# scheme-mkii.net
KiCad netlist of a schematic drawn in Altium Designer
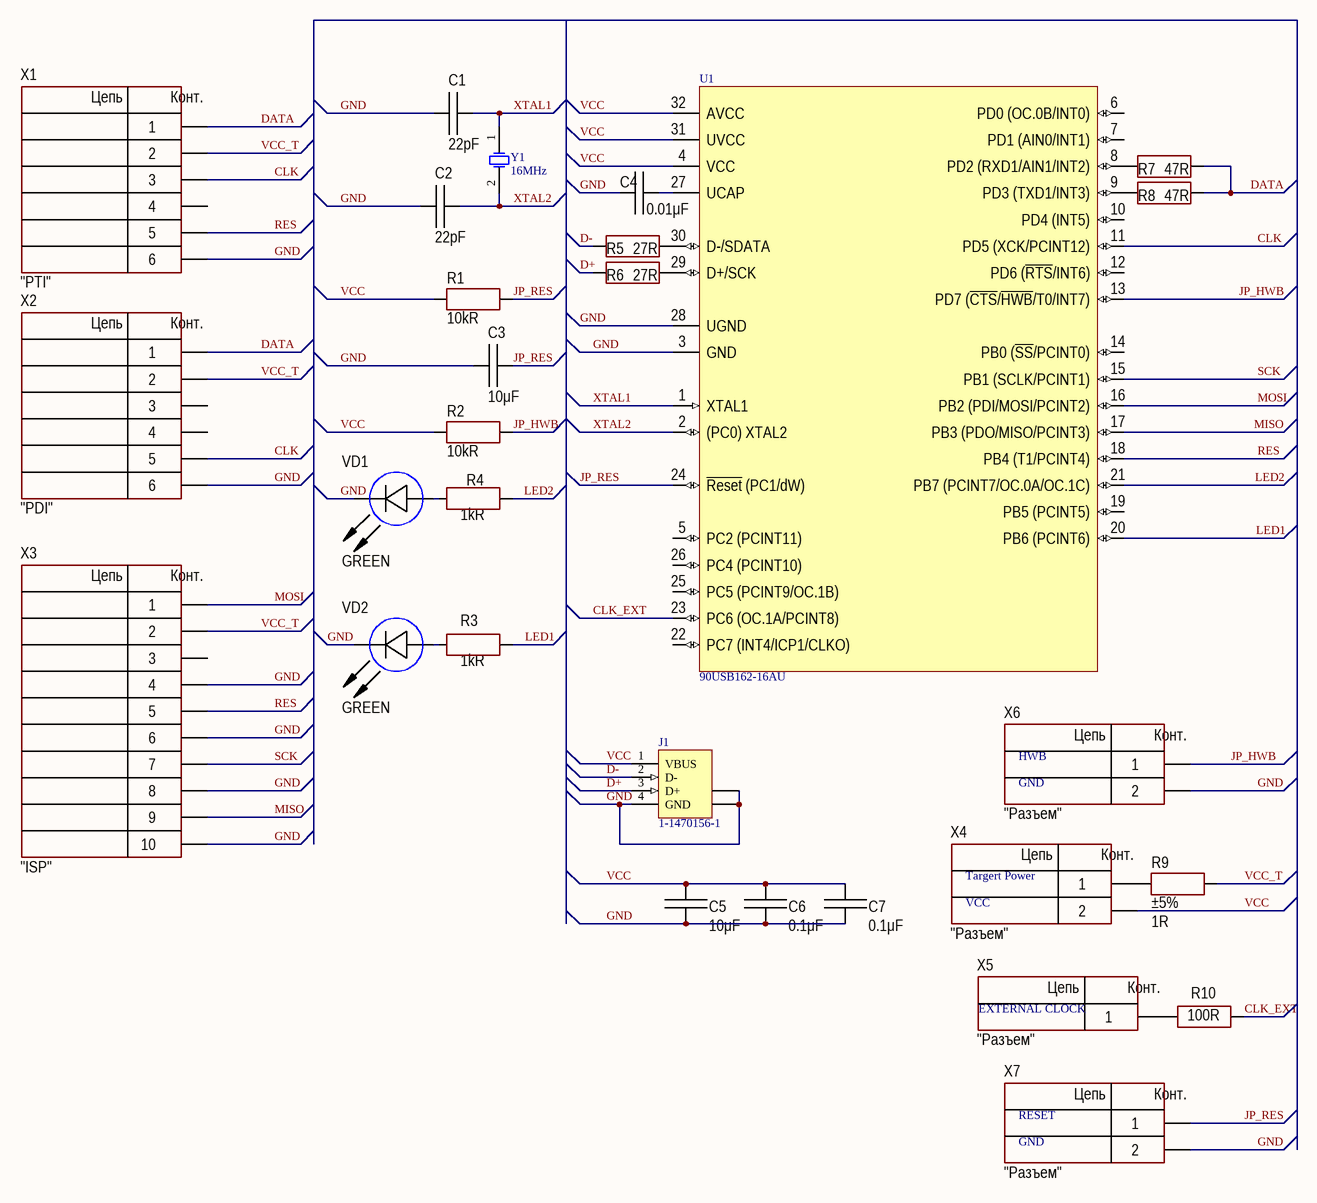
[diagram p0: scheme-mkii.SchDoc]

(export (version "E")
  (design (tool "Eeschema 10.0.6"))
  (components
    (comp (ref "C1")
      (value "22pF")
      (footprint "CAP: 0805")
      (fields
        (field (name "MANUFACTURER") "Yageo")
        (field (name "PARTNUMBER") "CC0805KRX7R7BB104")
        (field (name "VALUEMANUFACTURERPARTNUMBER") "Ceramic capacitor, 22pF, X7R, ±10%, 16V, 0805, -55...+125°C")
      )
      (libsource (lib "Capacitor") (part "Ceramic_0805"))
    )
    (comp (ref "C2")
      (value "22pF")
      (footprint "CAP: 0805")
      (fields
        (field (name "MANUFACTURER") "Yageo")
        (field (name "PARTNUMBER") "CC0805KRX7R7BB104")
        (field (name "VALUEMANUFACTURERPARTNUMBER") "Ceramic capacitor, 22pF, X7R, ±10%, 16V, 0805, -55...+125°C")
      )
      (libsource (lib "Capacitor") (part "Ceramic_0805"))
    )
    (comp (ref "C3")
      (value "10μF")
      (footprint "CAP: 0805")
      (fields
        (field (name "MANUFACTURER") "Yageo")
        (field (name "PARTNUMBER") "CC0805KRX7R7BB104")
        (field (name "VALUEMANUFACTURERPARTNUMBER") "Ceramic capacitor, 10μF, X7R, ±10%, 16V, 0805, -55...+125°C")
      )
      (libsource (lib "Capacitor") (part "Ceramic_0805"))
    )
    (comp (ref "C4")
      (value "0.01μF")
      (footprint "CAP: 0805")
      (fields
        (field (name "MANUFACTURER") "Yageo")
        (field (name "PARTNUMBER") "CC0805KRX7R7BB104")
        (field (name "VALUEMANUFACTURERPARTNUMBER") "Ceramic capacitor, 0.01μF, X7R, ±10%, 16V, 0805, -55...+125°C")
      )
      (libsource (lib "Capacitor") (part "Ceramic_0805"))
    )
    (comp (ref "C5")
      (value "10μF")
      (footprint "CAP: 0805")
      (fields
        (field (name "MANUFACTURER") "Yageo")
        (field (name "PARTNUMBER") "CC0805KRX7R7BB104")
        (field (name "VALUEMANUFACTURERPARTNUMBER") "Ceramic capacitor, 10μF, X7R, ±10%, 16V, 0805, -55...+125°C")
      )
      (libsource (lib "Capacitor") (part "Ceramic_0805"))
    )
    (comp (ref "C6")
      (value "0.1μF")
      (footprint "CAP: 0805")
      (fields
        (field (name "MANUFACTURER") "Yageo")
        (field (name "PARTNUMBER") "CC0805KRX7R7BB104")
        (field (name "VALUEMANUFACTURERPARTNUMBER") "Ceramic capacitor, 0.1μF, X7R, ±10%, 16V, 0805, -55...+125°C")
      )
      (libsource (lib "Capacitor") (part "Ceramic_0805"))
    )
    (comp (ref "C7")
      (value "0.1μF")
      (footprint "CAP: 0805")
      (fields
        (field (name "MANUFACTURER") "Yageo")
        (field (name "PARTNUMBER") "CC0805KRX7R7BB104")
        (field (name "VALUEMANUFACTURERPARTNUMBER") "Ceramic capacitor, 0.1μF, X7R, ±10%, 16V, 0805, -55...+125°C")
      )
      (libsource (lib "Capacitor") (part "Ceramic_0805"))
    )
    (comp (ref "J1")
      (value "1-1470156-1")
      (footprint "1-1470156")
      (description "USB 1.1, Right Angle, Thru-Hole, B Type, Receptacle, 4 Position, White")
      (fields (field (name "PUBLISHER") "Altium Limited"))
      (libsource (lib "AMP Serial Bus USB") (part "1-1470156-1"))
    )
    (comp (ref "R1")
      (value "10kR")
      (footprint "RES: 0402")
      (fields
        (field (name "MANUFACTURER") "Yageo")
        (field (name "PARTNUMBER") "RC0402JR-07100RL")
        (field (name "VALUEMANUFACTURERPARTNUMBER") "Resistor film, 10kR, ±5%, 0402, 0.063W, -55...+125°C")
      )
      (libsource (lib "") (part "Resistor_0402_1"))
    )
    (comp (ref "R2")
      (value "10kR")
      (footprint "RES: 0402")
      (fields
        (field (name "MANUFACTURER") "Yageo")
        (field (name "PARTNUMBER") "RC0402JR-07100RL")
        (field (name "VALUEMANUFACTURERPARTNUMBER") "Resistor film, 10kR, ±5%, 0402, 0.063W, -55...+125°C")
      )
      (libsource (lib "") (part "Resistor_0402_1"))
    )
    (comp (ref "R3")
      (value "1kR")
      (footprint "RES: 0402")
      (fields
        (field (name "MANUFACTURER") "Yageo")
        (field (name "PARTNUMBER") "RC0402JR-07100RL")
        (field (name "VALUEMANUFACTURERPARTNUMBER") "Resistor film, 1kR, ±5%, 0402, 0.063W, -55...+125°C")
      )
      (libsource (lib "Resistor") (part "Resistor_0402"))
    )
    (comp (ref "R4")
      (value "1kR")
      (footprint "RES: 0402")
      (fields
        (field (name "MANUFACTURER") "Yageo")
        (field (name "PARTNUMBER") "RC0402JR-07100RL")
        (field (name "VALUEMANUFACTURERPARTNUMBER") "Resistor film, 1kR, ±5%, 0402, 0.063W, -55...+125°C")
      )
      (libsource (lib "Resistor") (part "Resistor_0402"))
    )
    (comp (ref "R5")
      (value "27R")
      (footprint "RES: 0402")
      (fields
        (field (name "MANUFACTURER") "Yageo")
        (field (name "PARTNUMBER") "RC0402JR-07100RL")
        (field (name "VALUEMANUFACTURERPARTNUMBER") "Resistor film, 27R, ±5%, 0402, 0.063W, -55...+125°C")
      )
      (libsource (lib "Resistor") (part "Resistor_0402"))
    )
    (comp (ref "R6")
      (value "27R")
      (footprint "RES: 0402")
      (fields
        (field (name "MANUFACTURER") "Yageo")
        (field (name "PARTNUMBER") "RC0402JR-07100RL")
        (field (name "VALUEMANUFACTURERPARTNUMBER") "Resistor film, 27R, ±5%, 0402, 0.063W, -55...+125°C")
      )
      (libsource (lib "Resistor") (part "Resistor_0402"))
    )
    (comp (ref "R7")
      (value "47R")
      (footprint "RES: 0402")
      (fields
        (field (name "MANUFACTURER") "Yageo")
        (field (name "PARTNUMBER") "RC0402JR-07100RL")
        (field (name "VALUEMANUFACTURERPARTNUMBER") "Resistor film, 47R, ±5%, 0402, 0.063W, -55...+125°C")
      )
      (libsource (lib "Resistor") (part "Resistor_0402"))
    )
    (comp (ref "R8")
      (value "47R")
      (footprint "RES: 0402")
      (fields
        (field (name "MANUFACTURER") "Yageo")
        (field (name "PARTNUMBER") "RC0402JR-07100RL")
        (field (name "VALUEMANUFACTURERPARTNUMBER") "Resistor film, 47R, ±5%, 0402, 0.063W, -55...+125°C")
      )
      (libsource (lib "Resistor") (part "Resistor_0402"))
    )
    (comp (ref "R9")
      (value "1R")
      (footprint "RES: 0402")
      (fields
        (field (name "MANUFACTURER") "Yageo")
        (field (name "PARTNUMBER") "RC0402JR-07100RL")
        (field (name "VALUEMANUFACTURERPARTNUMBER") "Resistor film, 1R, ±5%, 0402, 0.063W, -55...+125°C")
        (field (name "TOLERANCE") "±5%")
      )
      (libsource (lib "Resistor") (part "Resistor_0402"))
    )
    (comp (ref "R10")
      (value "100R")
      (footprint "RES: 0402")
      (fields
        (field (name "MANUFACTURER") "Yageo")
        (field (name "PARTNUMBER") "RC0402JR-07100RL")
        (field (name "VALUEMANUFACTURERPARTNUMBER") "Resistor film, 100R, ±5%, 0402, 0.063W, -55...+125°C")
      )
      (libsource (lib "Resistor") (part "Resistor_0402"))
    )
    (comp (ref "U1")
      (value "90USB162-16AU")
      (footprint "32MA_N")
      (libsource (lib "Atmel Microcontroller megaAVR") (part "90USB162-16AU"))
    )
    (comp (ref "VD1")
      (value "~")
      (footprint "LED: 0402B")
      (fields
        (field (name "VALUEMANUFACTURERPARTNUMBER") "LED, *, *, *, -55...+150°C")
        (field (name "COLOR") "GREEN")
      )
      (libsource (lib "Diode") (part "LED_single"))
    )
    (comp (ref "VD2")
      (value "~")
      (footprint "LED: 0402B")
      (fields
        (field (name "VALUEMANUFACTURERPARTNUMBER") "LED, *, *, *, -55...+150°C")
        (field (name "COLOR") "GREEN")
      )
      (libsource (lib "Diode") (part "LED_single"))
    )
    (comp (ref "X1")
      (value "~")
      (footprint "CON: IDC-6MS")
      (fields
        (field (name "MANUFACTURER") "Connfly")
        (field (name "VALUEMANUFACTURERPARTNUMBER") "Connector, 6pin, 2.54mm, 250VAC, 3A")
        (field (name "PARTNUMBER") "IDC-6")
        (field (name "COMMENTTEXT") "\"PTI\"")
      )
      (libsource (lib "Connector") (part "IDC-6"))
    )
    (comp (ref "X2")
      (value "~")
      (footprint "CON: IDC-6MS")
      (fields
        (field (name "MANUFACTURER") "Connfly")
        (field (name "VALUEMANUFACTURERPARTNUMBER") "Connector, 6pin, 2.54mm, 250VAC, 3A")
        (field (name "PARTNUMBER") "IDC-6")
        (field (name "COMMENTTEXT") "\"PDI\"")
      )
      (libsource (lib "Connector") (part "IDC-6"))
    )
    (comp (ref "X3")
      (value "~")
      (footprint "CON: IDC-10MS")
      (fields
        (field (name "MANUFACTURER") "Connfly")
        (field (name "VALUEMANUFACTURERPARTNUMBER") "Connector, 10pin, 2.54mm, 250VAC, 3A")
        (field (name "PARTNUMBER") "IDC-10")
        (field (name "COMMENTTEXT") "\"ISP\"")
      )
      (libsource (lib "Connector") (part "IDC-10"))
    )
    (comp (ref "X4")
      (value "~")
      (footprint "CON: PLS-2")
      (fields
        (field (name "MANUFACTURER") "Connfly")
        (field (name "VALUEMANUFACTURERPARTNUMBER") "Connector, 2pin, 2.54mm, 500VAC, 3A")
        (field (name "PARTNUMBER") "PLS-2")
        (field (name "COMMENTTEXT") "\"Разъем\"")
        (field (name "COMMENTTEXT_1") "Targert Power")
        (field (name "COMMENTTEXT_2") "VCC")
      )
      (libsource (lib "Connector") (part "PLS-2"))
    )
    (comp (ref "X5")
      (value "~")
      (footprint "CON: PLS-1")
      (fields
        (field (name "MANUFACTURER") "Connfly")
        (field (name "VALUEMANUFACTURERPARTNUMBER") "Connector, 2pin, 2.54mm, 500VAC, 3A")
        (field (name "PARTNUMBER") "PLS-1")
        (field (name "COMMENTTEXT") "\"Разъем\"")
        (field (name "ALTIUM_UNNAMED_1") "EXTERNAL CLOCK")
      )
      (libsource (lib "Connector") (part "PLS-1"))
    )
    (comp (ref "X6")
      (value "~")
      (footprint "CON: PLS-2")
      (fields
        (field (name "MANUFACTURER") "Connfly")
        (field (name "VALUEMANUFACTURERPARTNUMBER") "Connector, 2pin, 2.54mm, 500VAC, 3A")
        (field (name "PARTNUMBER") "PLS-2")
        (field (name "COMMENTTEXT") "\"Разъем\"")
        (field (name "COMMENTTEXT_1") "HWB")
        (field (name "COMMENTTEXT_2") "GND")
      )
      (libsource (lib "Connector") (part "PLS-2"))
    )
    (comp (ref "X7")
      (value "~")
      (footprint "CON: PLS-2")
      (fields
        (field (name "MANUFACTURER") "Connfly")
        (field (name "VALUEMANUFACTURERPARTNUMBER") "Connector, 2pin, 2.54mm, 500VAC, 3A")
        (field (name "PARTNUMBER") "PLS-2")
        (field (name "COMMENTTEXT") "\"Разъем\"")
        (field (name "COMMENTTEXT_1") "RESET")
        (field (name "COMMENTTEXT_2") "GND")
      )
      (libsource (lib "Connector") (part "PLS-2"))
    )
    (comp (ref "Y1")
      (value "16MHz")
      (footprint "HC-49U")
      (description "Crystal Oscillator")
      (fields (field (name "PUBLISHER") "Altium Limited"))
      (libsource (lib "ECS Crystal Oscillator") (part "ECS-10-13-1"))
    )
  )
  (nets
    (net (code "1") (name "/CLK") (class "Default")
      (node (ref "U1") (pin "11") (pinfunction "PD5_(XCK/PCINT12)_11") (pintype "bidirectional"))
      (node (ref "X1") (pin "3") (pinfunction "3_3") (pintype "power_in"))
      (node (ref "X2") (pin "5") (pinfunction "5_5") (pintype "power_in"))
    )
    (net (code "2") (name "/CLK_EXT") (class "Default")
      (node (ref "R10") (pin "2") (pinfunction "2_2") (pintype "passive"))
      (node (ref "U1") (pin "23") (pinfunction "PC6_(OC.1A/PCINT8)_23") (pintype "bidirectional"))
    )
    (net (code "3") (name "/D+") (class "Default")
      (node (ref "J1") (pin "3") (pinfunction "D+_3") (pintype "input"))
      (node (ref "R6") (pin "1") (pinfunction "1_1") (pintype "passive"))
    )
    (net (code "4") (name "/D-") (class "Default")
      (node (ref "J1") (pin "2") (pinfunction "D-_2") (pintype "input"))
      (node (ref "R5") (pin "1") (pinfunction "1_1") (pintype "passive"))
    )
    (net (code "5") (name "/DATA") (class "Default")
      (node (ref "R7") (pin "2") (pinfunction "2_2") (pintype "passive"))
      (node (ref "R8") (pin "2") (pinfunction "2_2") (pintype "passive"))
      (node (ref "X1") (pin "1") (pinfunction "1_1") (pintype "passive"))
      (node (ref "X2") (pin "1") (pinfunction "1_1") (pintype "passive"))
    )
    (net (code "6") (name "/GND") (class "Default")
      (node (ref "C1") (pin "1") (pinfunction "1_1") (pintype "power_in"))
      (node (ref "C2") (pin "1") (pinfunction "1_1") (pintype "power_in"))
      (node (ref "C3") (pin "1") (pinfunction "1_1") (pintype "power_in"))
      (node (ref "C4") (pin "2") (pinfunction "2_2") (pintype "power_in"))
      (node (ref "C5") (pin "2") (pinfunction "2_2") (pintype "power_in"))
      (node (ref "C6") (pin "2") (pinfunction "2_2") (pintype "power_in"))
      (node (ref "C7") (pin "2") (pinfunction "2_2") (pintype "power_in"))
      (node (ref "J1") (pin "4") (pinfunction "GND_4") (pintype "power_in"))
      (node (ref "J1") (pin "5") (pinfunction "SHLD_5") (pintype "passive"))
      (node (ref "J1") (pin "6") (pinfunction "SHLD_6") (pintype "passive"))
      (node (ref "U1") (pin "28") (pinfunction "UGND_28") (pintype "power_in"))
      (node (ref "U1") (pin "3") (pinfunction "GND_3") (pintype "power_in"))
      (node (ref "VD1") (pin "2") (pinfunction "C_2") (pintype "passive"))
      (node (ref "VD2") (pin "2") (pinfunction "C_2") (pintype "passive"))
      (node (ref "X1") (pin "6") (pinfunction "6_6") (pintype "power_in"))
      (node (ref "X2") (pin "6") (pinfunction "6_6") (pintype "power_in"))
      (node (ref "X3") (pin "10") (pinfunction "10_10") (pintype "power_in"))
      (node (ref "X3") (pin "4") (pinfunction "4_4") (pintype "power_in"))
      (node (ref "X3") (pin "6") (pinfunction "6_6") (pintype "power_in"))
      (node (ref "X3") (pin "8") (pinfunction "8_8") (pintype "power_in"))
      (node (ref "X6") (pin "2") (pinfunction "2_2") (pintype "passive"))
      (node (ref "X7") (pin "2") (pinfunction "2_2") (pintype "passive"))
    )
    (net (code "7") (name "/JP_HWB") (class "Default")
      (node (ref "R2") (pin "1") (pinfunction "1_1") (pintype "passive"))
      (node (ref "U1") (pin "13") (pinfunction "PD7_(~{CTS}/~{HWB}/T0/INT7)_13") (pintype "bidirectional"))
      (node (ref "X6") (pin "1") (pinfunction "1_1") (pintype "passive"))
    )
    (net (code "8") (name "/JP_RES") (class "Default")
      (node (ref "C3") (pin "2") (pinfunction "2_2") (pintype "power_in"))
      (node (ref "R1") (pin "1") (pinfunction "1_1") (pintype "passive"))
      (node (ref "U1") (pin "24") (pinfunction "~{Reset}_(PC1/dW)_24") (pintype "bidirectional"))
      (node (ref "X7") (pin "1") (pinfunction "1_1") (pintype "passive"))
    )
    (net (code "9") (name "/LED1") (class "Default")
      (node (ref "R3") (pin "2") (pinfunction "2_2") (pintype "passive"))
      (node (ref "U1") (pin "20") (pinfunction "PB6_(PCINT6)_20") (pintype "bidirectional"))
    )
    (net (code "10") (name "/LED2") (class "Default")
      (node (ref "R4") (pin "2") (pinfunction "2_2") (pintype "passive"))
      (node (ref "U1") (pin "21") (pinfunction "PB7_(PCINT7/OC.0A/OC.1C)_21") (pintype "bidirectional"))
    )
    (net (code "11") (name "/MISO") (class "Default")
      (node (ref "U1") (pin "17") (pinfunction "PB3_(PDO/MISO/PCINT3)_17") (pintype "bidirectional"))
      (node (ref "X3") (pin "9") (pinfunction "9_9") (pintype "power_in"))
    )
    (net (code "12") (name "/MOSI") (class "Default")
      (node (ref "U1") (pin "16") (pinfunction "PB2_(PDI/MOSI/PCINT2)_16") (pintype "bidirectional"))
      (node (ref "X3") (pin "1") (pinfunction "1_1") (pintype "passive"))
    )
    (net (code "13") (name "/RES") (class "Default")
      (node (ref "U1") (pin "18") (pinfunction "PB4_(T1/PCINT4)_18") (pintype "bidirectional"))
      (node (ref "X1") (pin "5") (pinfunction "5_5") (pintype "power_in"))
      (node (ref "X3") (pin "5") (pinfunction "5_5") (pintype "power_in"))
    )
    (net (code "14") (name "/SCK") (class "Default")
      (node (ref "U1") (pin "15") (pinfunction "PB1_(SCLK/PCINT1)_15") (pintype "bidirectional"))
      (node (ref "X3") (pin "7") (pinfunction "7_7") (pintype "power_in"))
    )
    (net (code "15") (name "/VCC") (class "Default")
      (node (ref "C5") (pin "1") (pinfunction "1_1") (pintype "power_in"))
      (node (ref "C6") (pin "1") (pinfunction "1_1") (pintype "power_in"))
      (node (ref "C7") (pin "1") (pinfunction "1_1") (pintype "power_in"))
      (node (ref "J1") (pin "1") (pinfunction "VBUS_1") (pintype "power_in"))
      (node (ref "R1") (pin "2") (pinfunction "2_2") (pintype "passive"))
      (node (ref "R2") (pin "2") (pinfunction "2_2") (pintype "passive"))
      (node (ref "U1") (pin "31") (pinfunction "UVCC_31") (pintype "power_in"))
      (node (ref "U1") (pin "32") (pinfunction "AVCC_32") (pintype "power_in"))
      (node (ref "U1") (pin "4") (pinfunction "VCC_4") (pintype "power_in"))
      (node (ref "X4") (pin "2") (pinfunction "2_2") (pintype "passive"))
    )
    (net (code "16") (name "/VCC_T") (class "Default")
      (node (ref "R9") (pin "2") (pinfunction "2_2") (pintype "passive"))
      (node (ref "X1") (pin "2") (pinfunction "2_2") (pintype "passive"))
      (node (ref "X2") (pin "2") (pinfunction "2_2") (pintype "passive"))
      (node (ref "X3") (pin "2") (pinfunction "2_2") (pintype "passive"))
    )
    (net (code "17") (name "/XTAL1") (class "Default")
      (node (ref "C1") (pin "2") (pinfunction "2_2") (pintype "power_in"))
      (node (ref "U1") (pin "1") (pinfunction "XTAL1_1") (pintype "input"))
      (node (ref "Y1") (pin "1") (pinfunction "OSC1_1") (pintype "passive"))
    )
    (net (code "18") (name "/XTAL2") (class "Default")
      (node (ref "C2") (pin "2") (pinfunction "2_2") (pintype "power_in"))
      (node (ref "U1") (pin "2") (pinfunction "(PC0)_XTAL2_2") (pintype "bidirectional"))
      (node (ref "Y1") (pin "2") (pinfunction "OSC2_2") (pintype "passive"))
    )
    (net (code "19") (name "Net-(R9-Pad1)") (class "Default")
      (node (ref "R9") (pin "1") (pinfunction "1_1") (pintype "passive"))
      (node (ref "X4") (pin "1") (pinfunction "1_1") (pintype "passive"))
    )
    (net (code "20") (name "Net-(R10-Pad1)") (class "Default")
      (node (ref "R10") (pin "1") (pinfunction "1_1") (pintype "passive"))
      (node (ref "X5") (pin "1") (pinfunction "1_1") (pintype "passive"))
    )
    (net (code "21") (name "Net-(U1-D+{slash}SCK)") (class "Default")
      (node (ref "R6") (pin "2") (pinfunction "2_2") (pintype "passive"))
      (node (ref "U1") (pin "29") (pinfunction "D+/SCK_29") (pintype "bidirectional"))
    )
    (net (code "22") (name "Net-(U1-D-{slash}SDATA)") (class "Default")
      (node (ref "R5") (pin "2") (pinfunction "2_2") (pintype "passive"))
      (node (ref "U1") (pin "30") (pinfunction "D-/SDATA_30") (pintype "bidirectional"))
    )
    (net (code "23") (name "Net-(U1-PD2_(RXD1{slash}AIN1{slash}INT2))") (class "Default")
      (node (ref "R7") (pin "1") (pinfunction "1_1") (pintype "passive"))
      (node (ref "U1") (pin "8") (pinfunction "PD2_(RXD1/AIN1/INT2)_8") (pintype "bidirectional"))
    )
    (net (code "24") (name "Net-(U1-PD3_(TXD1{slash}INT3))") (class "Default")
      (node (ref "R8") (pin "1") (pinfunction "1_1") (pintype "passive"))
      (node (ref "U1") (pin "9") (pinfunction "PD3_(TXD1/INT3)_9") (pintype "bidirectional"))
    )
    (net (code "25") (name "Net-(U1-UCAP)") (class "Default")
      (node (ref "C4") (pin "1") (pinfunction "1_1") (pintype "power_in"))
      (node (ref "U1") (pin "27") (pinfunction "UCAP_27") (pintype "power_in"))
    )
    (net (code "26") (name "Net-(VD1-A)") (class "Default")
      (node (ref "R4") (pin "1") (pinfunction "1_1") (pintype "passive"))
      (node (ref "VD1") (pin "1") (pinfunction "A_1") (pintype "passive"))
    )
    (net (code "27") (name "Net-(VD2-A)") (class "Default")
      (node (ref "R3") (pin "1") (pinfunction "1_1") (pintype "passive"))
      (node (ref "VD2") (pin "1") (pinfunction "A_1") (pintype "passive"))
    )
    (net (code "28") (name "unconnected-(U1-PB0_(~{SS}{slash}PCINT0)-Pad14)") (class "Default")
      (node (ref "U1") (pin "14") (pinfunction "PB0_(~{SS}/PCINT0)_14") (pintype "bidirectional"))
    )
    (net (code "29") (name "unconnected-(U1-PB5_(PCINT5)-Pad19)") (class "Default")
      (node (ref "U1") (pin "19") (pinfunction "PB5_(PCINT5)_19") (pintype "bidirectional"))
    )
    (net (code "30") (name "unconnected-(U1-PC2_(PCINT11)-Pad5)") (class "Default")
      (node (ref "U1") (pin "5") (pinfunction "PC2_(PCINT11)_5") (pintype "bidirectional"))
    )
    (net (code "31") (name "unconnected-(U1-PC4_(PCINT10)-Pad26)") (class "Default")
      (node (ref "U1") (pin "26") (pinfunction "PC4_(PCINT10)_26") (pintype "bidirectional"))
    )
    (net (code "32") (name "unconnected-(U1-PC5_(PCINT9{slash}OC.1B)-Pad25)") (class "Default")
      (node (ref "U1") (pin "25") (pinfunction "PC5_(PCINT9/OC.1B)_25") (pintype "bidirectional"))
    )
    (net (code "33") (name "unconnected-(U1-PC7_(INT4{slash}ICP1{slash}CLKO)-Pad22)") (class "Default")
      (node (ref "U1") (pin "22") (pinfunction "PC7_(INT4/ICP1/CLKO)_22") (pintype "bidirectional"))
    )
    (net (code "34") (name "unconnected-(U1-PD0_(OC.0B{slash}INT0)-Pad6)") (class "Default")
      (node (ref "U1") (pin "6") (pinfunction "PD0_(OC.0B/INT0)_6") (pintype "bidirectional"))
    )
    (net (code "35") (name "unconnected-(U1-PD1_(AIN0{slash}INT1)-Pad7)") (class "Default")
      (node (ref "U1") (pin "7") (pinfunction "PD1_(AIN0/INT1)_7") (pintype "bidirectional"))
    )
    (net (code "36") (name "unconnected-(U1-PD4_(INT5)-Pad10)") (class "Default")
      (node (ref "U1") (pin "10") (pinfunction "PD4_(INT5)_10") (pintype "bidirectional"))
    )
    (net (code "37") (name "unconnected-(U1-PD6_(~{RTS}{slash}INT6)-Pad12)") (class "Default")
      (node (ref "U1") (pin "12") (pinfunction "PD6_(~{RTS}/INT6)_12") (pintype "bidirectional"))
    )
    (net (code "38") (name "unconnected-(X1-Pad4)") (class "Default")
      (node (ref "X1") (pin "4") (pinfunction "4_4") (pintype "power_in"))
    )
    (net (code "39") (name "unconnected-(X2-Pad3)") (class "Default")
      (node (ref "X2") (pin "3") (pinfunction "3_3") (pintype "power_in"))
    )
    (net (code "40") (name "unconnected-(X2-Pad4)") (class "Default")
      (node (ref "X2") (pin "4") (pinfunction "4_4") (pintype "power_in"))
    )
    (net (code "41") (name "unconnected-(X3-Pad3)") (class "Default")
      (node (ref "X3") (pin "3") (pinfunction "3_3") (pintype "power_in"))
    )
  )
)
